# 12V_POWER.net
KiCad netlist of a schematic drawn in Altium Designer
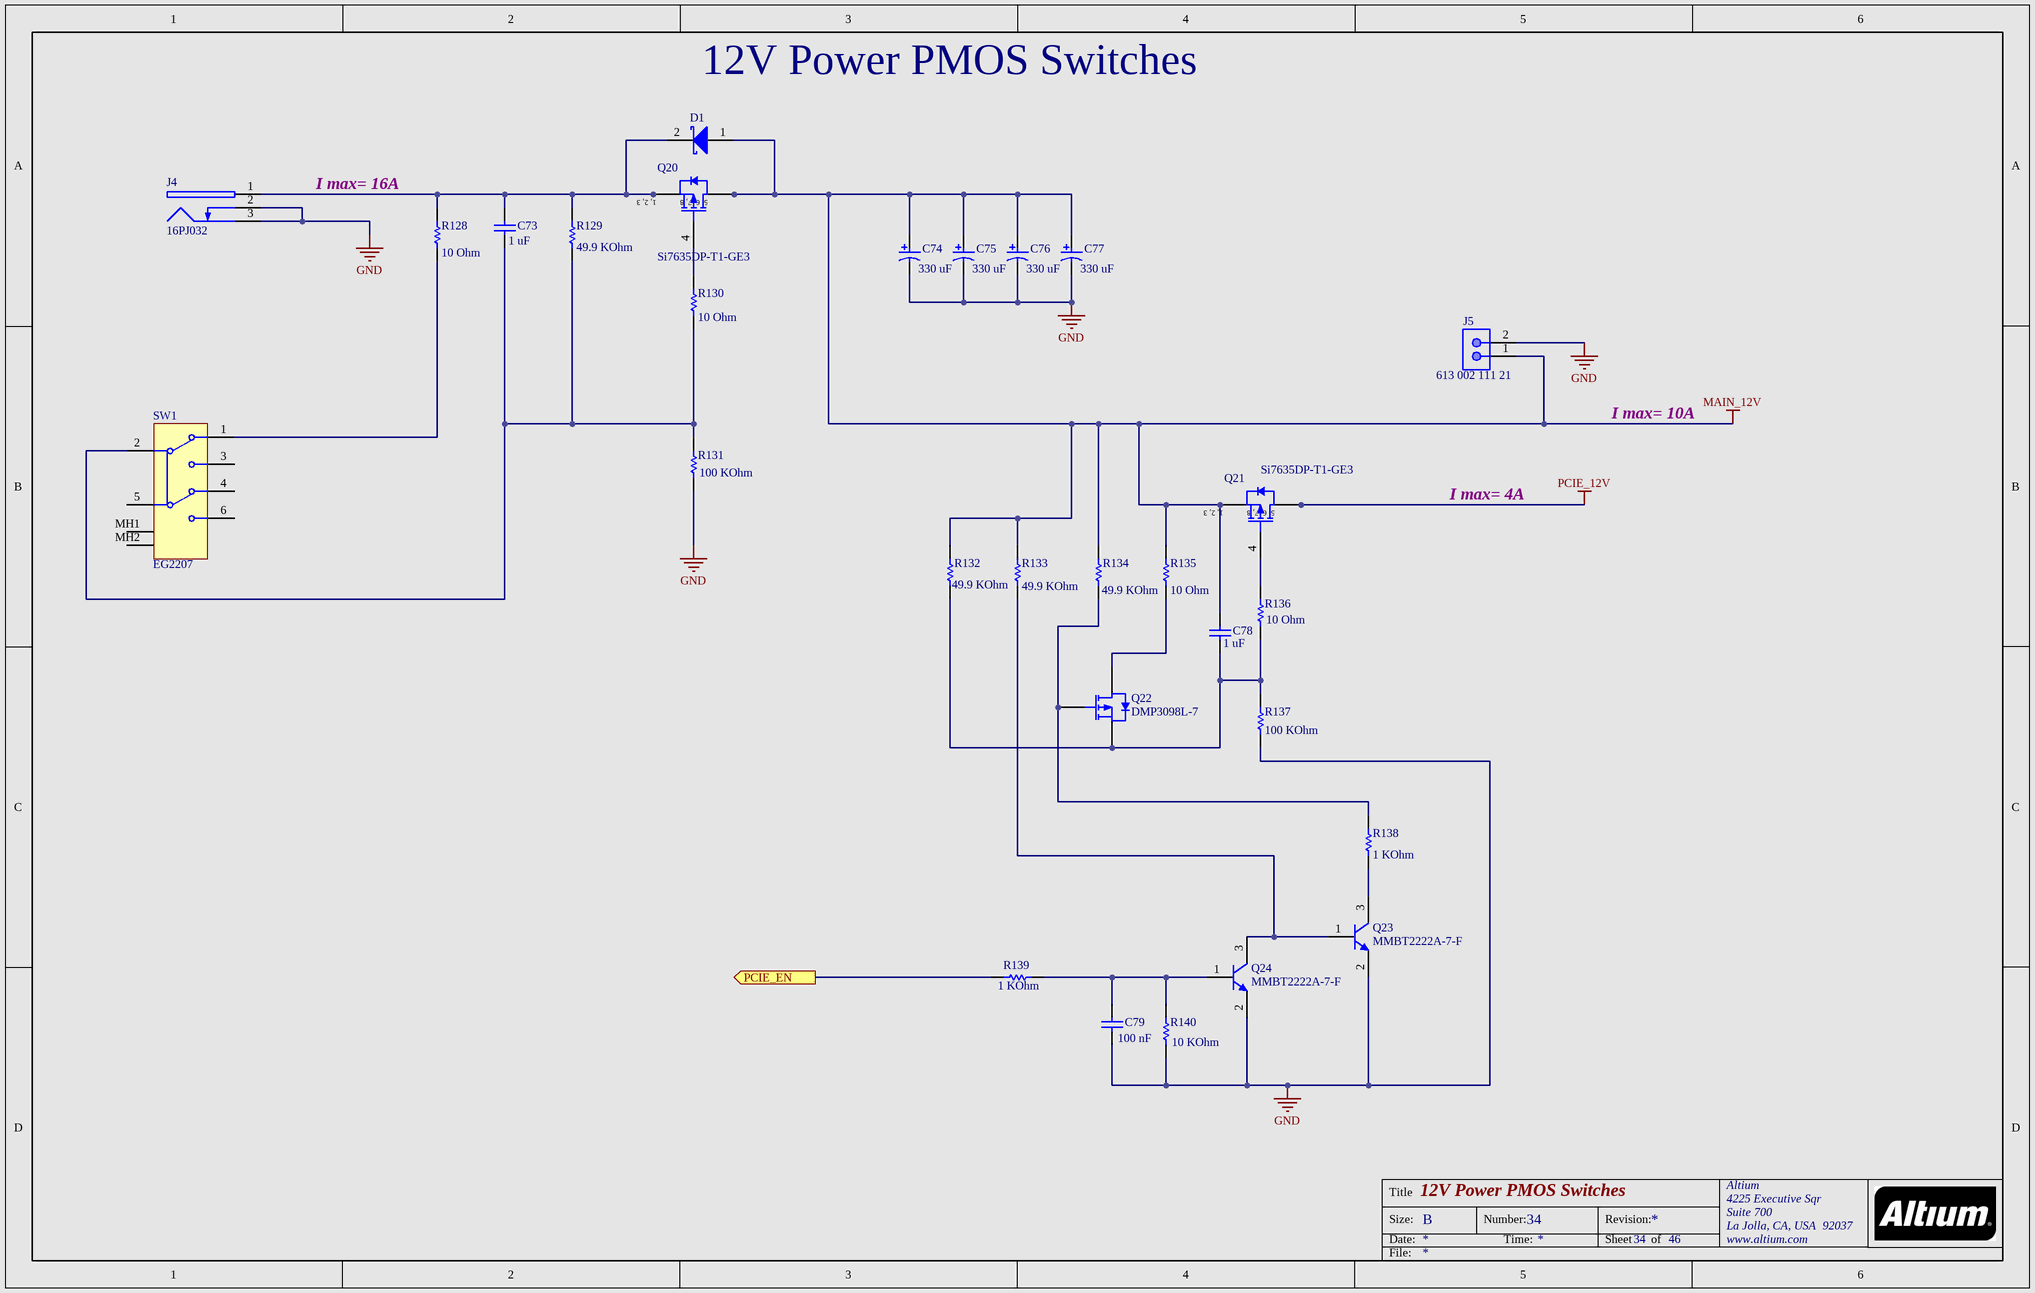
[diagram p0: 12V_POWER.SchDoc]

(export (version "E")
  (design (tool "Eeschema 10.0.6"))
  (components
    (comp (ref "C73")
      (value "CGB2A1X5R1E105K033BC")
      (footprint "CAPC1005X33X10LL5")
      (description "Chip Capacitor, 1 uF, +/- 10%, 25 V, -55 to 85 degC, 0402 (1005 Metric), RoHS, Tape and Reel")
      (fields (field (name "TOLERANCE") "10%") (field (name "CAPACITANCE") "1 uF"))
      (libsource (lib "Altium Content Vault") (part "CMP-1663-00006-2"))
    )
    (comp (ref "C74")
      (value "EEH-ZA1E331P")
      (footprint "PNSC-EEH-ZA1E331P_M")
      (fields (field (name "CAPACITANCE") "330 uF") (field (name "TOLERANCE") "20%"))
      (libsource (lib "Altium Content Vault") (part "CMP-1665-00032-1"))
    )
    (comp (ref "C75")
      (value "EEH-ZA1E331P")
      (footprint "PNSC-EEH-ZA1E331P_M")
      (fields (field (name "CAPACITANCE") "330 uF") (field (name "TOLERANCE") "20%"))
      (libsource (lib "Altium Content Vault") (part "CMP-1665-00032-1"))
    )
    (comp (ref "C76")
      (value "EEH-ZA1E331P")
      (footprint "PNSC-EEH-ZA1E331P_M")
      (fields (field (name "CAPACITANCE") "330 uF") (field (name "TOLERANCE") "20%"))
      (libsource (lib "Altium Content Vault") (part "CMP-1665-00032-1"))
    )
    (comp (ref "C77")
      (value "EEH-ZA1E331P")
      (footprint "PNSC-EEH-ZA1E331P_M")
      (fields (field (name "CAPACITANCE") "330 uF") (field (name "TOLERANCE") "20%"))
      (libsource (lib "Altium Content Vault") (part "CMP-1665-00032-1"))
    )
    (comp (ref "C78")
      (value "CGB2A1X5R1E105K033BC")
      (footprint "CAPC1005X33X10LL5")
      (description "Chip Capacitor, 1 uF, +/- 10%, 25 V, -55 to 85 degC, 0402 (1005 Metric), RoHS, Tape and Reel")
      (fields (field (name "TOLERANCE") "10%") (field (name "CAPACITANCE") "1 uF"))
      (libsource (lib "Altium Content Vault") (part "CMP-1663-00006-2"))
    )
    (comp (ref "C79")
      (value "C1005X7R1E104M")
      (footprint "CAPC1005X55X10LL05")
      (description "Chip Capacitor, 0.1 uF, +/- 20%, 25 V, -55 to 125 degC, 0402 (1005 Metric), RoHS, Tape and Reel")
      (fields (field (name "TOLERANCE") "20%") (field (name "CAPACITANCE") "100 nF"))
      (libsource (lib "Altium Content Vault") (part "CAP-NP-2"))
    )
    (comp (ref "D1")
      (value "B530C-13-F")
      (footprint "DIOD-SMC-2_V")
      (fields (field (name "MANUFACTURER") "Diodes Inc"))
      (libsource (lib "Altium Content Vault") (part "CMP-1693-00001-1"))
    )
    (comp (ref "J4")
      (value "16PJ032")
      (footprint "KOBI-16PJ032_V")
      (description "DC Power Jack, Female, -10 to 70 degC, 3-Pin THD, RoHS")
      (libsource (lib "Altium Content Vault") (part "JACK-2CD3-RN_A"))
    )
    (comp (ref "J5")
      (value "613 002 111 21")
      (footprint "WE-61300211121_V")
      (fields (field (name "MANUFACTURER") "Wuerth Elektronik"))
      (libsource (lib "Altium Content Vault") (part "CMP-1712-00002-1"))
    )
    (comp (ref "Q20")
      (value "Si7635DP-T1-GE3")
      (footprint "VISH-PPAKSO-8_V")
      (description "P-Channel MOSFET, 20 V, -55 to 150 degC, 8-Pin SMD (PPAKSO-8), RoHS, Tape and Reel")
      (libsource (lib "Altium Content Vault") (part "PEMOS-SSSGDDDD-8"))
    )
    (comp (ref "Q21")
      (value "Si7635DP-T1-GE3")
      (footprint "VISH-PPAKSO-8_V")
      (description "P-Channel MOSFET, 20 V, -55 to 150 degC, 8-Pin SMD (PPAKSO-8), RoHS, Tape and Reel")
      (libsource (lib "Altium Content Vault") (part "PEMOS-SSSGDDDD-8"))
    )
    (comp (ref "Q22")
      (value "DMP3098L-7")
      (footprint "DIOD-SOT23-3_V")
      (description "P-Channel Enhancement Mode MOSFET, -30 V VDS, -55 to 155 degC, 3-Pin SOT23, RoHS, Tape and Reel")
      (fields (field (name "MANUFACTURER") "Diodes Inc"))
      (libsource (lib "Altium Content Vault") (part "DIOD-PEMOS-G1S2D3-3"))
    )
    (comp (ref "Q23")
      (value "MMBT2222A-7-F")
      (footprint "DIOD-SOT23-3_V")
      (description "NPN Small Signal Transistor, 40 V, -55 to 150 degC, 3-Pin SOT23, RoHS, Tape and Reel")
      (fields (field (name "MANUFACTURER") "Diodes Inc"))
      (libsource (lib "Altium Content Vault") (part "BJT-NPN-BEC-3"))
    )
    (comp (ref "Q24")
      (value "MMBT2222A-7-F")
      (footprint "DIOD-SOT23-3_V")
      (description "NPN Small Signal Transistor, 40 V, -55 to 150 degC, 3-Pin SOT23, RoHS, Tape and Reel")
      (fields (field (name "MANUFACTURER") "Diodes Inc"))
      (libsource (lib "Altium Content Vault") (part "BJT-NPN-BEC-3"))
    )
    (comp (ref "R128")
      (value "ERJ-2RKF10R0X")
      (footprint "RESC1005X40X25LL05T05")
      (description "Chip Resistor, 10 Ohm, +/- 1%, 100 mW, -55 to 155 degC, 0402 (1005 Metric), RoHS, Tape and Reel")
      (fields
        (field (name "RESISTANCE") "10 Ohm")
        (field (name "TOLERANCE") "1%")
        (field (name "MANUFACTURER") "Basic Passives")
      )
      (libsource (lib "Altium Content Vault") (part "RES-2"))
    )
    (comp (ref "R129")
      (value "ERJ-2RKF4992X")
      (footprint "RESC1005X40X25LL05T05")
      (description "Chip Resistor, 49.9 KOhm, +/- 1%, 100 mW, -55 to 155 degC, 0402 (1005 Metric), RoHS, Tape and Reel")
      (fields
        (field (name "TOLERANCE") "1%")
        (field (name "RESISTANCE") "49.9 KOhm")
        (field (name "MANUFACTURER") "Basic Passives")
      )
      (libsource (lib "Altium Content Vault") (part "RES-2"))
    )
    (comp (ref "R130")
      (value "ERJ-2RKF10R0X")
      (footprint "RESC1005X40X25LL05T05")
      (description "Chip Resistor, 10 Ohm, +/- 1%, 100 mW, -55 to 155 degC, 0402 (1005 Metric), RoHS, Tape and Reel")
      (fields
        (field (name "RESISTANCE") "10 Ohm")
        (field (name "TOLERANCE") "1%")
        (field (name "MANUFACTURER") "Basic Passives")
      )
      (libsource (lib "Altium Content Vault") (part "RES-2"))
    )
    (comp (ref "R131")
      (value "ERJ-2RKF1003X")
      (footprint "RESC1005X40X25LL05T05")
      (description "Chip Resistor, 100 KOhm, +/- 1%, 100 mW, -55 to 155 degC, 0402 (1005 Metric), RoHS, Tape and Reel")
      (fields
        (field (name "RESISTANCE") "100 KOhm")
        (field (name "TOLERANCE") "1%")
        (field (name "MANUFACTURER") "Basic Passives")
      )
      (libsource (lib "Altium Content Vault") (part "RES-2"))
    )
    (comp (ref "R132")
      (value "ERJ-2RKF4992X")
      (footprint "RESC1005X40X25LL05T05")
      (description "Chip Resistor, 49.9 KOhm, +/- 1%, 100 mW, -55 to 155 degC, 0402 (1005 Metric), RoHS, Tape and Reel")
      (fields
        (field (name "TOLERANCE") "1%")
        (field (name "RESISTANCE") "49.9 KOhm")
        (field (name "MANUFACTURER") "Basic Passives")
      )
      (libsource (lib "Altium Content Vault") (part "RES-2"))
    )
    (comp (ref "R133")
      (value "ERJ-2RKF4992X")
      (footprint "RESC1005X40X25LL05T05")
      (description "Chip Resistor, 49.9 KOhm, +/- 1%, 100 mW, -55 to 155 degC, 0402 (1005 Metric), RoHS, Tape and Reel")
      (fields
        (field (name "TOLERANCE") "1%")
        (field (name "RESISTANCE") "49.9 KOhm")
        (field (name "MANUFACTURER") "Basic Passives")
      )
      (libsource (lib "Altium Content Vault") (part "RES-2"))
    )
    (comp (ref "R134")
      (value "ERJ-2RKF4992X")
      (footprint "RESC1005X40X25LL05T05")
      (description "Chip Resistor, 49.9 KOhm, +/- 1%, 100 mW, -55 to 155 degC, 0402 (1005 Metric), RoHS, Tape and Reel")
      (fields
        (field (name "TOLERANCE") "1%")
        (field (name "RESISTANCE") "49.9 KOhm")
        (field (name "MANUFACTURER") "Basic Passives")
      )
      (libsource (lib "Altium Content Vault") (part "RES-2"))
    )
    (comp (ref "R135")
      (value "ERJ-2RKF10R0X")
      (footprint "RESC1005X40X25LL05T05")
      (description "Chip Resistor, 10 Ohm, +/- 1%, 100 mW, -55 to 155 degC, 0402 (1005 Metric), RoHS, Tape and Reel")
      (fields
        (field (name "RESISTANCE") "10 Ohm")
        (field (name "TOLERANCE") "1%")
        (field (name "MANUFACTURER") "Basic Passives")
      )
      (libsource (lib "Altium Content Vault") (part "RES-2"))
    )
    (comp (ref "R136")
      (value "ERJ-2RKF10R0X")
      (footprint "RESC1005X40X25LL05T05")
      (description "Chip Resistor, 10 Ohm, +/- 1%, 100 mW, -55 to 155 degC, 0402 (1005 Metric), RoHS, Tape and Reel")
      (fields
        (field (name "RESISTANCE") "10 Ohm")
        (field (name "TOLERANCE") "1%")
        (field (name "MANUFACTURER") "Basic Passives")
      )
      (libsource (lib "Altium Content Vault") (part "RES-2"))
    )
    (comp (ref "R137")
      (value "ERJ-2RKF1003X")
      (footprint "RESC1005X40X25LL05T05")
      (description "Chip Resistor, 100 KOhm, +/- 1%, 100 mW, -55 to 155 degC, 0402 (1005 Metric), RoHS, Tape and Reel")
      (fields
        (field (name "RESISTANCE") "100 KOhm")
        (field (name "TOLERANCE") "1%")
        (field (name "MANUFACTURER") "Basic Passives")
      )
      (libsource (lib "Altium Content Vault") (part "RES-2"))
    )
    (comp (ref "R138")
      (value "ERJ-2RKF1001X")
      (footprint "RESC1005X40X25LL05T05")
      (description "Chip Resistor, 1 KOhm, +/- 1%, 100 mW, -55 to 155 degC, 0402 (1005 Metric), RoHS, Tape and Reel")
      (fields
        (field (name "RESISTANCE") "1 KOhm")
        (field (name "TOLERANCE") "1%")
        (field (name "MANUFACTURER") "Basic Passives")
      )
      (libsource (lib "Altium Content Vault") (part "RES-2"))
    )
    (comp (ref "R139")
      (value "ERJ-2RKF1001X")
      (footprint "RESC1005X40X25LL05T05")
      (description "Chip Resistor, 1 KOhm, +/- 1%, 100 mW, -55 to 155 degC, 0402 (1005 Metric), RoHS, Tape and Reel")
      (fields
        (field (name "RESISTANCE") "1 KOhm")
        (field (name "TOLERANCE") "1%")
        (field (name "MANUFACTURER") "Basic Passives")
      )
      (libsource (lib "Altium Content Vault") (part "RES-2"))
    )
    (comp (ref "R140")
      (value "ERJ-2RKF1002X")
      (footprint "RESC1005X40X25NL05T05")
      (description "Chip Resistor, 10 KOhm, +/- 1%, 100 mW, -55 to 155 degC, 0402 (1005 Metric), RoHS, Tape and Reel")
      (fields
        (field (name "TOLERANCE") "1%")
        (field (name "RESISTANCE") "10 KOhm")
        (field (name "MANUFACTURER") "Basic Passives")
      )
      (libsource (lib "Altium Content Vault") (part "RES-2"))
    )
    (comp (ref "SW1")
      (value "EG2207")
      (footprint "ESWI-EG2207_V")
      (description "Slide Switch DPDT, 30 V, -20 to 70 degC, 6-Pin THD, RoHS, Bulk")
      (libsource (lib "Altium Content Vault") (part "SW-DPDT-6"))
    )
  )
  (nets
    (net (code "1") (name "/PCIE_EN") (class "Default")
      (node (ref "R139") (pin "1") (pinfunction "1_1") (pintype "passive"))
    )
    (net (code "2") (name "GND") (class "Default")
      (node (ref "C74") (pin "2") (pinfunction "2_2") (pintype "passive"))
      (node (ref "C75") (pin "2") (pinfunction "2_2") (pintype "passive"))
      (node (ref "C76") (pin "2") (pinfunction "2_2") (pintype "passive"))
      (node (ref "C77") (pin "2") (pinfunction "2_2") (pintype "passive"))
      (node (ref "C79") (pin "1") (pinfunction "1_1") (pintype "passive"))
      (node (ref "J4") (pin "2") (pinfunction "2_2") (pintype "passive"))
      (node (ref "J4") (pin "3") (pinfunction "3_3") (pintype "passive"))
      (node (ref "J5") (pin "2") (pinfunction "2_2") (pintype "passive"))
      (node (ref "Q23") (pin "2") (pinfunction "E_2") (pintype "passive"))
      (node (ref "Q24") (pin "2") (pinfunction "E_2") (pintype "passive"))
      (node (ref "R131") (pin "1") (pinfunction "1_1") (pintype "passive"))
      (node (ref "R137") (pin "1") (pinfunction "1_1") (pintype "passive"))
      (node (ref "R140") (pin "1") (pinfunction "1_1") (pintype "passive"))
    )
    (net (code "3") (name "MAIN_12V") (class "Default")
      (node (ref "C74") (pin "1") (pinfunction "1_1") (pintype "passive"))
      (node (ref "C75") (pin "1") (pinfunction "1_1") (pintype "passive"))
      (node (ref "C76") (pin "1") (pinfunction "1_1") (pintype "passive"))
      (node (ref "C77") (pin "1") (pinfunction "1_1") (pintype "passive"))
      (node (ref "C78") (pin "2") (pinfunction "2_2") (pintype "passive"))
      (node (ref "D1") (pin "1") (pinfunction "A_1") (pintype "passive"))
      (node (ref "J5") (pin "1") (pinfunction "1_1") (pintype "passive"))
      (node (ref "Q20") (pin "5") (pinfunction "D_5") (pintype "passive"))
      (node (ref "Q20") (pin "6") (pinfunction "D_6") (pintype "passive"))
      (node (ref "Q20") (pin "7") (pinfunction "D_7") (pintype "passive"))
      (node (ref "Q20") (pin "8") (pinfunction "D_8") (pintype "passive"))
      (node (ref "Q21") (pin "1") (pinfunction "S_1") (pintype "passive"))
      (node (ref "Q21") (pin "2") (pinfunction "S_2") (pintype "passive"))
      (node (ref "Q21") (pin "3") (pinfunction "S_3") (pintype "passive"))
      (node (ref "R132") (pin "2") (pinfunction "2_2") (pintype "passive"))
      (node (ref "R133") (pin "2") (pinfunction "2_2") (pintype "passive"))
      (node (ref "R134") (pin "2") (pinfunction "2_2") (pintype "passive"))
      (node (ref "R135") (pin "2") (pinfunction "2_2") (pintype "passive"))
    )
    (net (code "4") (name "Net-(C73-Pad1)") (class "Default")
      (node (ref "C73") (pin "1") (pinfunction "1_1") (pintype "passive"))
      (node (ref "R129") (pin "1") (pinfunction "1_1") (pintype "passive"))
      (node (ref "R130") (pin "1") (pinfunction "1_1") (pintype "passive"))
      (node (ref "R131") (pin "2") (pinfunction "2_2") (pintype "passive"))
      (node (ref "SW1") (pin "2") (pinfunction "2_2") (pintype "passive"))
    )
    (net (code "5") (name "Net-(D1-K)") (class "Default")
      (node (ref "C73") (pin "2") (pinfunction "2_2") (pintype "passive"))
      (node (ref "D1") (pin "2") (pinfunction "K_2") (pintype "passive"))
      (node (ref "J4") (pin "1") (pinfunction "1_1") (pintype "passive"))
      (node (ref "Q20") (pin "1") (pinfunction "S_1") (pintype "passive"))
      (node (ref "Q20") (pin "2") (pinfunction "S_2") (pintype "passive"))
      (node (ref "Q20") (pin "3") (pinfunction "S_3") (pintype "passive"))
      (node (ref "R128") (pin "2") (pinfunction "2_2") (pintype "passive"))
      (node (ref "R129") (pin "2") (pinfunction "2_2") (pintype "passive"))
    )
    (net (code "6") (name "Net-(Q20-G)") (class "Default")
      (node (ref "Q20") (pin "4") (pinfunction "G_4") (pintype "passive"))
      (node (ref "R130") (pin "2") (pinfunction "2_2") (pintype "passive"))
    )
    (net (code "7") (name "Net-(Q21-G)") (class "Default")
      (node (ref "Q21") (pin "4") (pinfunction "G_4") (pintype "passive"))
      (node (ref "R136") (pin "2") (pinfunction "2_2") (pintype "passive"))
    )
    (net (code "8") (name "Net-(Q22-D)") (class "Default")
      (node (ref "Q22") (pin "3") (pinfunction "D_3") (pintype "passive"))
      (node (ref "R135") (pin "1") (pinfunction "1_1") (pintype "passive"))
    )
    (net (code "9") (name "Net-(Q22-G)") (class "Default")
      (node (ref "Q22") (pin "1") (pinfunction "G_1") (pintype "passive"))
      (node (ref "R134") (pin "1") (pinfunction "1_1") (pintype "passive"))
      (node (ref "R138") (pin "2") (pinfunction "2_2") (pintype "passive"))
    )
    (net (code "10") (name "Net-(Q22-S)") (class "Default")
      (node (ref "C78") (pin "1") (pinfunction "1_1") (pintype "passive"))
      (node (ref "Q22") (pin "2") (pinfunction "S_2") (pintype "passive"))
      (node (ref "R132") (pin "1") (pinfunction "1_1") (pintype "passive"))
      (node (ref "R136") (pin "1") (pinfunction "1_1") (pintype "passive"))
      (node (ref "R137") (pin "2") (pinfunction "2_2") (pintype "passive"))
    )
    (net (code "11") (name "Net-(Q23-B)") (class "Default")
      (node (ref "Q23") (pin "1") (pinfunction "B_1") (pintype "passive"))
      (node (ref "Q24") (pin "3") (pinfunction "C_3") (pintype "passive"))
      (node (ref "R133") (pin "1") (pinfunction "1_1") (pintype "passive"))
    )
    (net (code "12") (name "Net-(Q23-C)") (class "Default")
      (node (ref "Q23") (pin "3") (pinfunction "C_3") (pintype "passive"))
      (node (ref "R138") (pin "1") (pinfunction "1_1") (pintype "passive"))
    )
    (net (code "13") (name "Net-(Q24-B)") (class "Default")
      (node (ref "C79") (pin "2") (pinfunction "2_2") (pintype "passive"))
      (node (ref "Q24") (pin "1") (pinfunction "B_1") (pintype "passive"))
      (node (ref "R139") (pin "2") (pinfunction "2_2") (pintype "passive"))
      (node (ref "R140") (pin "2") (pinfunction "2_2") (pintype "passive"))
    )
    (net (code "14") (name "Net-(R128-Pad1)") (class "Default")
      (node (ref "R128") (pin "1") (pinfunction "1_1") (pintype "passive"))
      (node (ref "SW1") (pin "1") (pinfunction "1_1") (pintype "passive"))
    )
    (net (code "15") (name "PCIE_12V") (class "Default")
      (node (ref "Q21") (pin "5") (pinfunction "D_5") (pintype "passive"))
      (node (ref "Q21") (pin "6") (pinfunction "D_6") (pintype "passive"))
      (node (ref "Q21") (pin "7") (pinfunction "D_7") (pintype "passive"))
      (node (ref "Q21") (pin "8") (pinfunction "D_8") (pintype "passive"))
    )
    (net (code "16") (name "unconnected-(SW1-Pad3)") (class "Default")
      (node (ref "SW1") (pin "3") (pinfunction "3_3") (pintype "passive"))
    )
    (net (code "17") (name "unconnected-(SW1-Pad4)") (class "Default")
      (node (ref "SW1") (pin "4") (pinfunction "4_4") (pintype "passive"))
    )
    (net (code "18") (name "unconnected-(SW1-Pad5)") (class "Default")
      (node (ref "SW1") (pin "5") (pinfunction "5_5") (pintype "passive"))
    )
    (net (code "19") (name "unconnected-(SW1-Pad6)") (class "Default")
      (node (ref "SW1") (pin "6") (pinfunction "6_6") (pintype "passive"))
    )
    (net (code "20") (name "unconnected-(SW1-PadMH1)") (class "Default")
      (node (ref "SW1") (pin "MH1") (pinfunction "MH1_MH1") (pintype "passive"))
    )
    (net (code "21") (name "unconnected-(SW1-PadMH2)") (class "Default")
      (node (ref "SW1") (pin "MH2") (pinfunction "MH2_MH2") (pintype "passive"))
    )
  )
)
